# Teensy_FrequencyShield_2ch.net
KiCad netlist of a schematic drawn in EAGLE
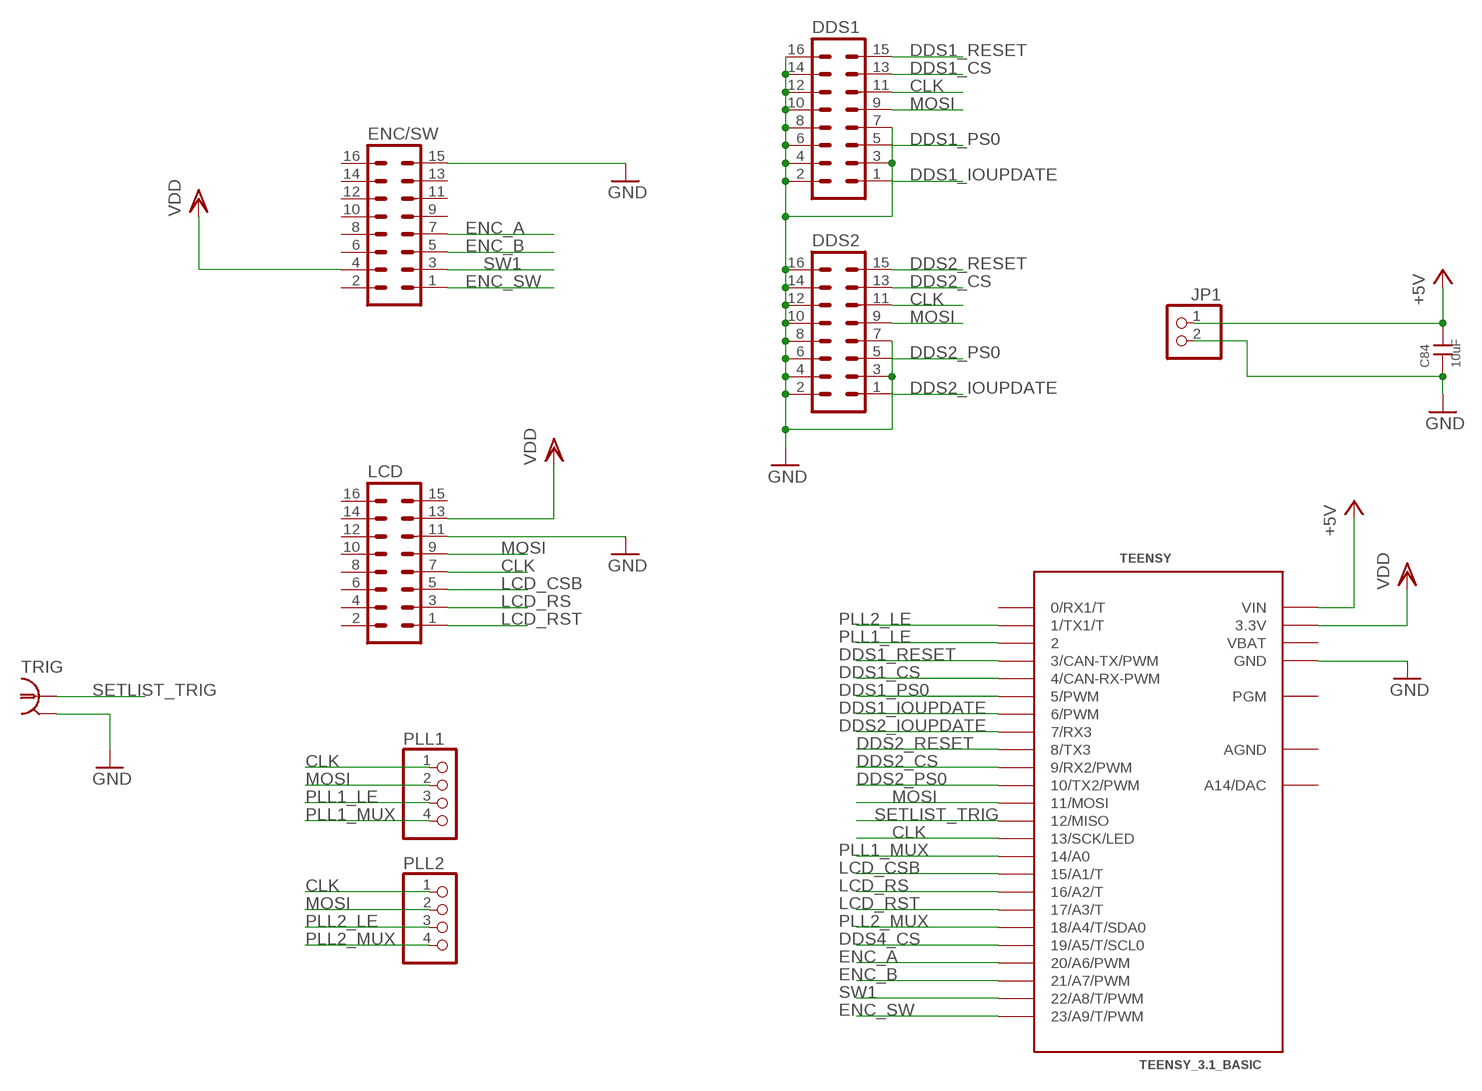
[diagram p0: schematic, sheet 1]

(export (version "E")
  (design (tool "Eeschema 10.0.6"))
  (components
    (comp (ref "C84")
      (value "10uF")
      (footprint "eagle-import:0805")
      (fields (field (name "PARTNO") "1276-2890-1-ND"))
      (libsource (lib "eagle-import") (part "CAP0805"))
    )
    (comp (ref "DDS1")
      (value "ML16")
      (footprint "eagle-import:ML16")
      (libsource (lib "eagle-import") (part "ML16"))
    )
    (comp (ref "DDS2")
      (value "ML16")
      (footprint "eagle-import:ML16")
      (libsource (lib "eagle-import") (part "ML16"))
    )
    (comp (ref "ENC/SW")
      (value "ML16")
      (footprint "eagle-import:ML16")
      (libsource (lib "eagle-import") (part "ML16"))
    )
    (comp (ref "JP1")
      (value "PINHD-1X2")
      (footprint "eagle-import:1X02")
      (libsource (lib "eagle-import") (part "PINHD-1X2"))
    )
    (comp (ref "LCD")
      (value "ML16")
      (footprint "eagle-import:ML16")
      (fields (field (name "PARTNO") "S9171-ND"))
      (libsource (lib "eagle-import") (part "ML16"))
    )
    (comp (ref "PLL1")
      (value "PINHD-1X4")
      (footprint "eagle-import:1X04")
      (libsource (lib "eagle-import") (part "PINHD-1X4"))
    )
    (comp (ref "PLL2")
      (value "PINHD-1X4")
      (footprint "eagle-import:1X04")
      (libsource (lib "eagle-import") (part "PINHD-1X4"))
    )
    (comp (ref "TEENSY")
      (value "TEENSY_3.1_BASIC")
      (footprint "eagle-import:TEENSY_3.1_BASIC")
      (libsource (lib "eagle-import") (part "TEENSY_3.1_BASIC"))
    )
    (comp (ref "TRIG")
      (value "BNC-H")
      (footprint "eagle-import:BNC90")
      (libsource (lib "eagle-import") (part "BNC-H"))
    )
  )
  (nets
    (net (code "1") (name "+5V") (class "Default")
      (node (ref "C84") (pin "2") (pinfunction "P$2_2") (pintype "passive"))
      (node (ref "JP1") (pin "1") (pinfunction "1_1") (pintype "passive"))
      (node (ref "TEENSY") (pin "VIN") (pinfunction "VIN_VIN") (pintype "power_in"))
    )
    (net (code "2") (name "/AGND") (class "Default")
      (node (ref "TEENSY") (pin "AGND") (pinfunction "AGND_AGND") (pintype "power_in"))
    )
    (net (code "3") (name "/CLK") (class "Default")
      (node (ref "DDS1") (pin "11") (pinfunction "11_11") (pintype "passive"))
      (node (ref "DDS2") (pin "11") (pinfunction "11_11") (pintype "passive"))
      (node (ref "LCD") (pin "7") (pinfunction "7_7") (pintype "passive"))
      (node (ref "PLL1") (pin "1") (pinfunction "1_1") (pintype "passive"))
      (node (ref "PLL2") (pin "1") (pinfunction "1_1") (pintype "passive"))
      (node (ref "TEENSY") (pin "13") (pinfunction "13/SCK/LED_13") (pintype "bidirectional"))
    )
    (net (code "4") (name "/DDS1_CS") (class "Default")
      (node (ref "DDS1") (pin "13") (pinfunction "13_13") (pintype "passive"))
      (node (ref "TEENSY") (pin "4") (pinfunction "4/CAN-RX-PWM_4") (pintype "bidirectional"))
    )
    (net (code "5") (name "/DDS1_IOUPDATE") (class "Default")
      (node (ref "DDS1") (pin "1") (pinfunction "1_1") (pintype "passive"))
      (node (ref "TEENSY") (pin "6") (pinfunction "6/PWM_6") (pintype "bidirectional"))
    )
    (net (code "6") (name "/DDS1_PS0") (class "Default")
      (node (ref "DDS1") (pin "5") (pinfunction "5_5") (pintype "passive"))
      (node (ref "TEENSY") (pin "5") (pinfunction "5/PWM_5") (pintype "bidirectional"))
    )
    (net (code "7") (name "/DDS1_RESET") (class "Default")
      (node (ref "DDS1") (pin "15") (pinfunction "15_15") (pintype "passive"))
      (node (ref "TEENSY") (pin "3") (pinfunction "3/CAN-TX/PWM_3") (pintype "bidirectional"))
    )
    (net (code "8") (name "/DDS2_CS") (class "Default")
      (node (ref "DDS2") (pin "13") (pinfunction "13_13") (pintype "passive"))
      (node (ref "TEENSY") (pin "9") (pinfunction "9/RX2/PWM_9") (pintype "bidirectional"))
    )
    (net (code "9") (name "/DDS2_IOUPDATE") (class "Default")
      (node (ref "DDS2") (pin "1") (pinfunction "1_1") (pintype "passive"))
      (node (ref "TEENSY") (pin "7") (pinfunction "7/RX3_7") (pintype "bidirectional"))
    )
    (net (code "10") (name "/DDS2_PS0") (class "Default")
      (node (ref "DDS2") (pin "5") (pinfunction "5_5") (pintype "passive"))
      (node (ref "TEENSY") (pin "10") (pinfunction "10/TX2/PWM_10") (pintype "bidirectional"))
    )
    (net (code "11") (name "/DDS2_RESET") (class "Default")
      (node (ref "DDS2") (pin "15") (pinfunction "15_15") (pintype "passive"))
      (node (ref "TEENSY") (pin "8") (pinfunction "8/TX3_8") (pintype "bidirectional"))
    )
    (net (code "12") (name "/DDS4_CS") (class "Default")
      (node (ref "TEENSY") (pin "19/A5") (pinfunction "19/A5/T/SCL0_19/A5") (pintype "bidirectional"))
    )
    (net (code "13") (name "/ENC_A") (class "Default")
      (node (ref "ENC/SW") (pin "7") (pinfunction "7_7") (pintype "passive"))
      (node (ref "TEENSY") (pin "20/A6") (pinfunction "20/A6/PWM_20/A6") (pintype "bidirectional"))
    )
    (net (code "14") (name "/ENC_B") (class "Default")
      (node (ref "ENC/SW") (pin "5") (pinfunction "5_5") (pintype "passive"))
      (node (ref "TEENSY") (pin "21/A7") (pinfunction "21/A7/PWM_21/A7") (pintype "bidirectional"))
    )
    (net (code "15") (name "/ENC_SW") (class "Default")
      (node (ref "ENC/SW") (pin "1") (pinfunction "1_1") (pintype "passive"))
      (node (ref "TEENSY") (pin "23/A9") (pinfunction "23/A9/T/PWM_23/A9") (pintype "bidirectional"))
    )
    (net (code "16") (name "/LCD_CSB") (class "Default")
      (node (ref "LCD") (pin "5") (pinfunction "5_5") (pintype "passive"))
      (node (ref "TEENSY") (pin "15/A1") (pinfunction "15/A1/T_15/A1") (pintype "bidirectional"))
    )
    (net (code "17") (name "/LCD_RS") (class "Default")
      (node (ref "LCD") (pin "3") (pinfunction "3_3") (pintype "passive"))
      (node (ref "TEENSY") (pin "16/A2") (pinfunction "16/A2/T_16/A2") (pintype "bidirectional"))
    )
    (net (code "18") (name "/LCD_RST") (class "Default")
      (node (ref "LCD") (pin "1") (pinfunction "1_1") (pintype "passive"))
      (node (ref "TEENSY") (pin "17/A3") (pinfunction "17/A3/T_17/A3") (pintype "bidirectional"))
    )
    (net (code "19") (name "/MOSI") (class "Default")
      (node (ref "DDS1") (pin "9") (pinfunction "9_9") (pintype "passive"))
      (node (ref "DDS2") (pin "9") (pinfunction "9_9") (pintype "passive"))
      (node (ref "LCD") (pin "9") (pinfunction "9_9") (pintype "passive"))
      (node (ref "PLL1") (pin "2") (pinfunction "2_2") (pintype "passive"))
      (node (ref "PLL2") (pin "2") (pinfunction "2_2") (pintype "passive"))
      (node (ref "TEENSY") (pin "11") (pinfunction "11/MOSI_11") (pintype "bidirectional"))
    )
    (net (code "20") (name "/PLL1_LE") (class "Default")
      (node (ref "PLL1") (pin "3") (pinfunction "3_3") (pintype "passive"))
      (node (ref "TEENSY") (pin "2") (pinfunction "2_2") (pintype "bidirectional"))
    )
    (net (code "21") (name "/PLL1_MUX") (class "Default")
      (node (ref "PLL1") (pin "4") (pinfunction "4_4") (pintype "passive"))
      (node (ref "TEENSY") (pin "14/A0") (pinfunction "14/A0_14/A0") (pintype "bidirectional"))
    )
    (net (code "22") (name "/PLL2_LE") (class "Default")
      (node (ref "PLL2") (pin "3") (pinfunction "3_3") (pintype "passive"))
      (node (ref "TEENSY") (pin "1") (pinfunction "1/TX1/T_1") (pintype "bidirectional"))
    )
    (net (code "23") (name "/PLL2_MUX") (class "Default")
      (node (ref "PLL2") (pin "4") (pinfunction "4_4") (pintype "passive"))
      (node (ref "TEENSY") (pin "18/A4") (pinfunction "18/A4/T/SDA0_18/A4") (pintype "bidirectional"))
    )
    (net (code "24") (name "/SETLIST_TRIG") (class "Default")
      (node (ref "TEENSY") (pin "12") (pinfunction "12/MISO_12") (pintype "bidirectional"))
      (node (ref "TRIG") (pin "1") (pinfunction "1_1") (pintype "passive"))
    )
    (net (code "25") (name "/SW1") (class "Default")
      (node (ref "ENC/SW") (pin "3") (pinfunction "3_3") (pintype "passive"))
      (node (ref "TEENSY") (pin "22/A8") (pinfunction "22/A8/T/PWM_22/A8") (pintype "bidirectional"))
    )
    (net (code "26") (name "/VBAT") (class "Default")
      (node (ref "TEENSY") (pin "VBAT") (pinfunction "VBAT_VBAT") (pintype "power_in"))
    )
    (net (code "27") (name "GND") (class "Default")
      (node (ref "C84") (pin "1") (pinfunction "P$1_1") (pintype "passive"))
      (node (ref "DDS1") (pin "10") (pinfunction "10_10") (pintype "passive"))
      (node (ref "DDS1") (pin "12") (pinfunction "12_12") (pintype "passive"))
      (node (ref "DDS1") (pin "14") (pinfunction "14_14") (pintype "passive"))
      (node (ref "DDS1") (pin "16") (pinfunction "16_16") (pintype "passive"))
      (node (ref "DDS1") (pin "2") (pinfunction "2_2") (pintype "passive"))
      (node (ref "DDS1") (pin "3") (pinfunction "3_3") (pintype "passive"))
      (node (ref "DDS1") (pin "4") (pinfunction "4_4") (pintype "passive"))
      (node (ref "DDS1") (pin "6") (pinfunction "6_6") (pintype "passive"))
      (node (ref "DDS1") (pin "7") (pinfunction "7_7") (pintype "passive"))
      (node (ref "DDS1") (pin "8") (pinfunction "8_8") (pintype "passive"))
      (node (ref "DDS2") (pin "10") (pinfunction "10_10") (pintype "passive"))
      (node (ref "DDS2") (pin "12") (pinfunction "12_12") (pintype "passive"))
      (node (ref "DDS2") (pin "14") (pinfunction "14_14") (pintype "passive"))
      (node (ref "DDS2") (pin "16") (pinfunction "16_16") (pintype "passive"))
      (node (ref "DDS2") (pin "2") (pinfunction "2_2") (pintype "passive"))
      (node (ref "DDS2") (pin "3") (pinfunction "3_3") (pintype "passive"))
      (node (ref "DDS2") (pin "4") (pinfunction "4_4") (pintype "passive"))
      (node (ref "DDS2") (pin "6") (pinfunction "6_6") (pintype "passive"))
      (node (ref "DDS2") (pin "7") (pinfunction "7_7") (pintype "passive"))
      (node (ref "DDS2") (pin "8") (pinfunction "8_8") (pintype "passive"))
      (node (ref "ENC/SW") (pin "15") (pinfunction "15_15") (pintype "passive"))
      (node (ref "JP1") (pin "2") (pinfunction "2_2") (pintype "passive"))
      (node (ref "LCD") (pin "11") (pinfunction "11_11") (pintype "passive"))
      (node (ref "TEENSY") (pin "GND") (pinfunction "GND_GND") (pintype "power_in"))
      (node (ref "TEENSY") (pin "GND1") (pinfunction "GND_GND1") (pintype "power_in"))
      (node (ref "TRIG") (pin "2") (pinfunction "2_2") (pintype "passive"))
    )
    (net (code "28") (name "VDD") (class "Default")
      (node (ref "ENC/SW") (pin "4") (pinfunction "4_4") (pintype "passive"))
      (node (ref "LCD") (pin "13") (pinfunction "13_13") (pintype "passive"))
      (node (ref "TEENSY") (pin "3.3V") (pinfunction "3.3V_3.3V") (pintype "power_in"))
      (node (ref "TEENSY") (pin "3.3V1") (pinfunction "3.3V_3.3V1") (pintype "power_in"))
    )
    (net (code "29") (name "unconnected-(ENC/SW-Pad2)") (class "Default")
      (node (ref "ENC/SW") (pin "2") (pinfunction "2_2") (pintype "passive"))
    )
    (net (code "30") (name "unconnected-(ENC/SW-Pad6)") (class "Default")
      (node (ref "ENC/SW") (pin "6") (pinfunction "6_6") (pintype "passive"))
    )
    (net (code "31") (name "unconnected-(ENC/SW-Pad8)") (class "Default")
      (node (ref "ENC/SW") (pin "8") (pinfunction "8_8") (pintype "passive"))
    )
    (net (code "32") (name "unconnected-(ENC/SW-Pad9)") (class "Default")
      (node (ref "ENC/SW") (pin "9") (pinfunction "9_9") (pintype "passive"))
    )
    (net (code "33") (name "unconnected-(ENC/SW-Pad10)") (class "Default")
      (node (ref "ENC/SW") (pin "10") (pinfunction "10_10") (pintype "passive"))
    )
    (net (code "34") (name "unconnected-(ENC/SW-Pad11)") (class "Default")
      (node (ref "ENC/SW") (pin "11") (pinfunction "11_11") (pintype "passive"))
    )
    (net (code "35") (name "unconnected-(ENC/SW-Pad12)") (class "Default")
      (node (ref "ENC/SW") (pin "12") (pinfunction "12_12") (pintype "passive"))
    )
    (net (code "36") (name "unconnected-(ENC/SW-Pad13)") (class "Default")
      (node (ref "ENC/SW") (pin "13") (pinfunction "13_13") (pintype "passive"))
    )
    (net (code "37") (name "unconnected-(ENC/SW-Pad14)") (class "Default")
      (node (ref "ENC/SW") (pin "14") (pinfunction "14_14") (pintype "passive"))
    )
    (net (code "38") (name "unconnected-(ENC/SW-Pad16)") (class "Default")
      (node (ref "ENC/SW") (pin "16") (pinfunction "16_16") (pintype "passive"))
    )
    (net (code "39") (name "unconnected-(LCD-Pad2)") (class "Default")
      (node (ref "LCD") (pin "2") (pinfunction "2_2") (pintype "passive"))
    )
    (net (code "40") (name "unconnected-(LCD-Pad4)") (class "Default")
      (node (ref "LCD") (pin "4") (pinfunction "4_4") (pintype "passive"))
    )
    (net (code "41") (name "unconnected-(LCD-Pad6)") (class "Default")
      (node (ref "LCD") (pin "6") (pinfunction "6_6") (pintype "passive"))
    )
    (net (code "42") (name "unconnected-(LCD-Pad8)") (class "Default")
      (node (ref "LCD") (pin "8") (pinfunction "8_8") (pintype "passive"))
    )
    (net (code "43") (name "unconnected-(LCD-Pad10)") (class "Default")
      (node (ref "LCD") (pin "10") (pinfunction "10_10") (pintype "passive"))
    )
    (net (code "44") (name "unconnected-(LCD-Pad12)") (class "Default")
      (node (ref "LCD") (pin "12") (pinfunction "12_12") (pintype "passive"))
    )
    (net (code "45") (name "unconnected-(LCD-Pad14)") (class "Default")
      (node (ref "LCD") (pin "14") (pinfunction "14_14") (pintype "passive"))
    )
    (net (code "46") (name "unconnected-(LCD-Pad15)") (class "Default")
      (node (ref "LCD") (pin "15") (pinfunction "15_15") (pintype "passive"))
    )
    (net (code "47") (name "unconnected-(LCD-Pad16)") (class "Default")
      (node (ref "LCD") (pin "16") (pinfunction "16_16") (pintype "passive"))
    )
    (net (code "48") (name "unconnected-(TEENSY-0{slash}RX1{slash}T-Pad0)") (class "Default")
      (node (ref "TEENSY") (pin "0") (pinfunction "0/RX1/T_0") (pintype "bidirectional"))
    )
    (net (code "49") (name "unconnected-(TEENSY-A14{slash}DAC-PadA14)") (class "Default")
      (node (ref "TEENSY") (pin "A14") (pinfunction "A14/DAC_A14") (pintype "bidirectional"))
    )
    (net (code "50") (name "unconnected-(TEENSY-PadPGM)") (class "Default")
      (node (ref "TEENSY") (pin "PGM") (pinfunction "PGM_PGM") (pintype "bidirectional"))
    )
  )
)
